# Microcontroller_sch_v22_4.net
KiCad netlist of a schematic drawn in Altium Designer
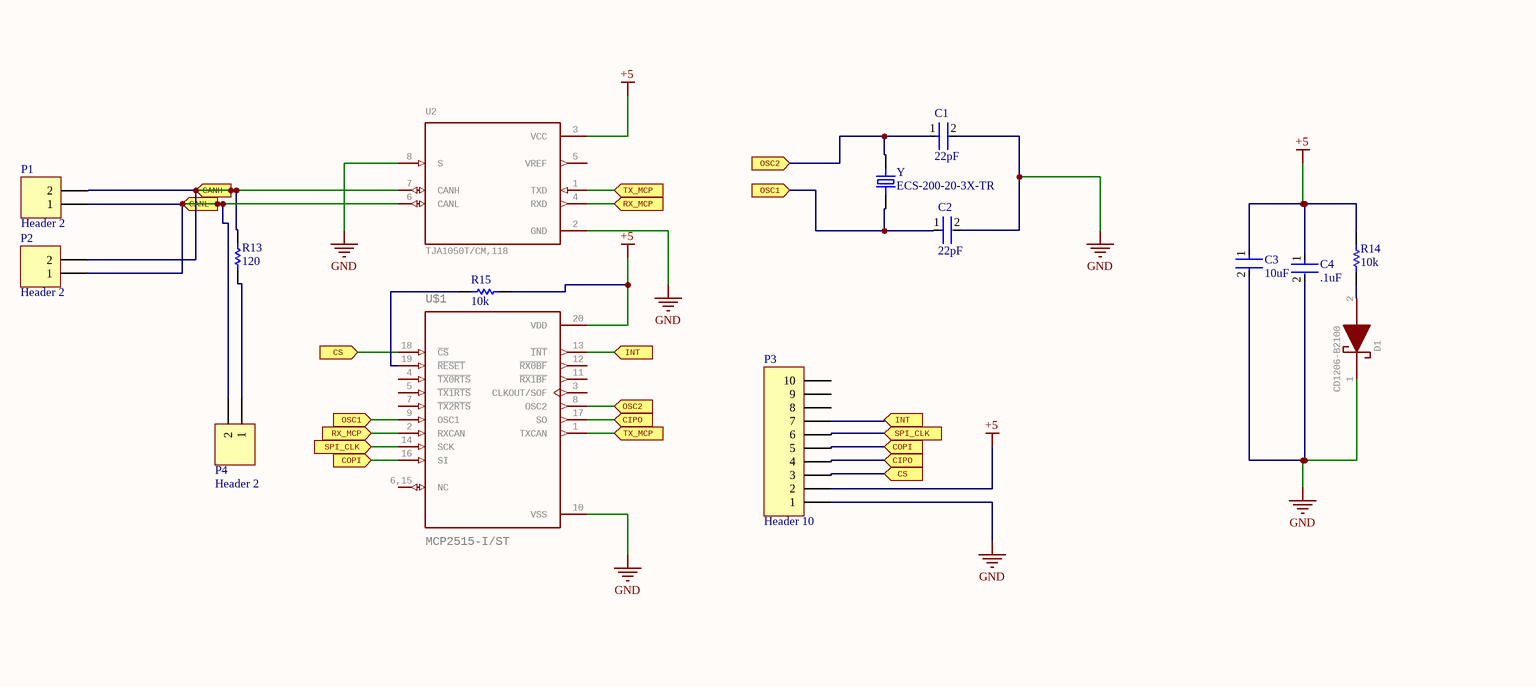
[diagram p0: Microcontroller_sch_v22_4.SchDoc]

(export (version "E")
  (design (tool "Eeschema 10.0.6"))
  (components
    (comp (ref "C1")
      (value "22pF")
      (footprint "FP-GRM21B-0_15-IPC_C")
      (description "Chip Multilayer Ceramic Capacitors for General Purpose, 0805, 10uF, X5R, 15%, 10%, 25V")
      (fields (field (name "VOLTAGE") "25V") (field (name "TOLERANCE") "10%"))
      (libsource (lib "Altium Content Vault") (part "b4654b650e69147ec39a6b967a45e02"))
    )
    (comp (ref "C2")
      (value "22pF")
      (footprint "FP-GRM21B-0_15-IPC_C")
      (description "Chip Multilayer Ceramic Capacitors for General Purpose, 0805, 10uF, X5R, 15%, 10%, 25V")
      (fields (field (name "VOLTAGE") "25V") (field (name "TOLERANCE") "10%"))
      (libsource (lib "Altium Content Vault") (part "b4654b650e69147ec39a6b967a45e02"))
    )
    (comp (ref "C3")
      (value "10uF")
      (footprint "FP-GRM21B-0_15-IPC_C")
      (description "Chip Multilayer Ceramic Capacitors for General Purpose, 0805, 10uF, X5R, 15%, 10%, 25V")
      (fields (field (name "VOLTAGE") "25V") (field (name "TOLERANCE") "10%"))
      (libsource (lib "Altium Content Vault") (part "b4654b650e69147ec39a6b967a45e02"))
    )
    (comp (ref "C4")
      (value ".1uF")
      (footprint "FP-GRM21B-0_15-IPC_C")
      (description "Chip Multilayer Ceramic Capacitors for General Purpose, 0805, 10uF, X5R, 15%, 10%, 25V")
      (fields (field (name "VOLTAGE") "25V") (field (name "TOLERANCE") "10%"))
      (libsource (lib "Altium Content Vault") (part "b4654b650e69147ec39a6b967a45e02"))
    )
    (comp (ref "D1")
      (value "CD1206-B2100")
      (footprint "DIOC3419X116N")
      (description "Schottky Diodes & Rectifiers CHIP DIODE   Source:  Datasheet")
      (fields (field (name "MOUSER_PART_NUMBER") "652-CD1206-B2100"))
      (libsource (lib "CD1206-B2100") (part "CD1206-B2100"))
    )
    (comp (ref "P1")
      (value "Header 2")
      (footprint "HDR1X2")
      (description "Header, 2-Pin")
      (fields (field (name "PUBLISHER") "Altium Limited"))
      (libsource (lib "") (part "Header 2_1"))
    )
    (comp (ref "P2")
      (value "Header 2")
      (footprint "HDR1X2")
      (description "Header, 2-Pin")
      (fields (field (name "PUBLISHER") "Altium Limited"))
      (libsource (lib "") (part "Header 2_1"))
    )
    (comp (ref "P3")
      (value "Header 10")
      (footprint "HDR1X10")
      (description "Header, 10-Pin")
      (fields (field (name "PUBLISHER") "Altium Limited"))
      (libsource (lib "Miscellaneous Connectors") (part "Header 10"))
    )
    (comp (ref "P4")
      (value "Header 2")
      (footprint "HDR1X2")
      (description "Header, 2-Pin")
      (fields (field (name "PUBLISHER") "Altium Limited"))
      (libsource (lib "Miscellaneous Connectors") (part "Header 2"))
    )
    (comp (ref "R13")
      (value "120")
      (footprint "RESC2013X50X30LL20T20")
      (fields (field (name "MANUFACTURER") "Vishay Dale") (field (name "PART NUMBER") "CRCW08050000Z0EA"))
      (libsource (lib "Altium Content Vault") (part "RES"))
    )
    (comp (ref "R14")
      (value "10k")
      (footprint "RESC2013X50X30LL20T20")
      (fields (field (name "MANUFACTURER") "Vishay Dale") (field (name "PART NUMBER") "CRCW08050000Z0EA"))
      (libsource (lib "Altium Content Vault") (part "RES"))
    )
    (comp (ref "R15")
      (value "10k")
      (footprint "RESC2013X50X30LL20T20")
      (fields (field (name "MANUFACTURER") "Vishay Dale") (field (name "PART NUMBER") "CRCW08050000Z0EA"))
      (libsource (lib "Altium Content Vault") (part "RES"))
    )
    (comp (ref "U$1")
      (value "MCP2515-I/ST")
      (footprint "SOP65P640X110-20N")
      (description "Check availability")
      (fields (field (name "MF") "Microchip"))
      (libsource (lib "MCP2515-I_ST") (part "MCP2515-I/ST"))
    )
    (comp (ref "U2")
      (value "TJA1050T/CM,118")
      (footprint "SOIC127P600X175-8N")
      (description "1/1 Transceiver Half CANbus 8-SO")
      (fields (field (name "MANUFACTURER") "NXP USA"))
      (libsource (lib "TJA1050T_CM_118") (part "TJA1050T/CM,118"))
    )
    (comp (ref "Y")
      (value "ECS-200-20-3X-TR")
      (footprint "XTAL_ECS-200-20-3X-TR")
      (description "20MHz Â± 30ppm Cristal 20pF 50 Ohms HC-49 / US")
      (fields (field (name "MF") "ECS Inc.") (field (name "DIGI-KEY_PART_NUMBER") "XC1779CT-ND"))
      (libsource (lib "ECS-200-20-3X-TR") (part "ECS-200-20-3X-TR"))
    )
  )
  (nets
    (net (code "1") (name "+5") (class "Default")
      (node (ref "C3") (pin "1") (pinfunction "1_1") (pintype "passive"))
      (node (ref "C4") (pin "1") (pinfunction "1_1") (pintype "passive"))
      (node (ref "P3") (pin "2") (pinfunction "2_2") (pintype "passive"))
      (node (ref "R14") (pin "1") (pinfunction "1_1") (pintype "passive"))
      (node (ref "R15") (pin "1") (pinfunction "1_1") (pintype "passive"))
      (node (ref "U$1") (pin "20") (pinfunction "VDD_20") (pintype "power_in"))
      (node (ref "U2") (pin "3") (pinfunction "VCC_3") (pintype "power_in"))
    )
    (net (code "2") (name "/CANH") (class "Default")
      (node (ref "P1") (pin "2") (pinfunction "2_2") (pintype "passive"))
      (node (ref "P2") (pin "2") (pinfunction "2_2") (pintype "passive"))
      (node (ref "R13") (pin "2") (pinfunction "2_2") (pintype "passive"))
      (node (ref "U2") (pin "7") (pinfunction "CANH_7") (pintype "bidirectional"))
    )
    (net (code "3") (name "/CANL") (class "Default")
      (node (ref "P1") (pin "1") (pinfunction "1_1") (pintype "passive"))
      (node (ref "P2") (pin "1") (pinfunction "1_1") (pintype "passive"))
      (node (ref "P4") (pin "2") (pinfunction "2_2") (pintype "passive"))
      (node (ref "U2") (pin "6") (pinfunction "CANL_6") (pintype "bidirectional"))
    )
    (net (code "4") (name "/CIPO") (class "Default")
      (node (ref "P3") (pin "4") (pinfunction "4_4") (pintype "passive"))
      (node (ref "U$1") (pin "17") (pinfunction "SO_17") (pintype "output"))
    )
    (net (code "5") (name "/COPI") (class "Default")
      (node (ref "P3") (pin "5") (pinfunction "5_5") (pintype "passive"))
      (node (ref "U$1") (pin "16") (pinfunction "SI_16") (pintype "input"))
    )
    (net (code "6") (name "/CS") (class "Default")
      (node (ref "P3") (pin "3") (pinfunction "3_3") (pintype "passive"))
      (node (ref "U$1") (pin "18") (pinfunction "~{CS}_18") (pintype "input"))
    )
    (net (code "7") (name "/INT") (class "Default")
      (node (ref "P3") (pin "7") (pinfunction "7_7") (pintype "passive"))
      (node (ref "U$1") (pin "13") (pinfunction "~{INT}_13") (pintype "output"))
    )
    (net (code "8") (name "/OSC1") (class "Default")
      (node (ref "C2") (pin "1") (pinfunction "1_1") (pintype "passive"))
      (node (ref "U$1") (pin "9") (pinfunction "OSC1_9") (pintype "input"))
      (node (ref "Y") (pin "1") (pinfunction "1_1") (pintype "passive"))
    )
    (net (code "9") (name "/OSC2") (class "Default")
      (node (ref "C1") (pin "1") (pinfunction "1_1") (pintype "passive"))
      (node (ref "U$1") (pin "8") (pinfunction "OSC2_8") (pintype "output"))
      (node (ref "Y") (pin "2") (pinfunction "2_2") (pintype "passive"))
    )
    (net (code "10") (name "/RX_MCP") (class "Default")
      (node (ref "U$1") (pin "2") (pinfunction "RXCAN_2") (pintype "input"))
      (node (ref "U2") (pin "4") (pinfunction "RXD_4") (pintype "output"))
    )
    (net (code "11") (name "/SPI_CLK") (class "Default")
      (node (ref "P3") (pin "6") (pinfunction "6_6") (pintype "passive"))
      (node (ref "U$1") (pin "14") (pinfunction "SCK_14") (pintype "input"))
    )
    (net (code "12") (name "/TX_MCP") (class "Default")
      (node (ref "U$1") (pin "1") (pinfunction "TXCAN_1") (pintype "output"))
      (node (ref "U2") (pin "1") (pinfunction "TXD_1") (pintype "input"))
    )
    (net (code "13") (name "GND") (class "Default")
      (node (ref "C1") (pin "2") (pinfunction "2_2") (pintype "passive"))
      (node (ref "C2") (pin "2") (pinfunction "2_2") (pintype "passive"))
      (node (ref "C3") (pin "2") (pinfunction "2_2") (pintype "passive"))
      (node (ref "C4") (pin "2") (pinfunction "2_2") (pintype "passive"))
      (node (ref "D1") (pin "1") (pinfunction "K_1") (pintype "bidirectional"))
      (node (ref "P3") (pin "1") (pinfunction "1_1") (pintype "passive"))
      (node (ref "U$1") (pin "10") (pinfunction "VSS_10") (pintype "power_in"))
      (node (ref "U2") (pin "2") (pinfunction "GND_2") (pintype "power_in"))
      (node (ref "U2") (pin "8") (pinfunction "S_8") (pintype "input"))
    )
    (net (code "14") (name "Net-(D1-A)") (class "Default")
      (node (ref "D1") (pin "2") (pinfunction "A_2") (pintype "bidirectional"))
      (node (ref "R14") (pin "2") (pinfunction "2_2") (pintype "passive"))
    )
    (net (code "15") (name "Net-(P4-Pad1)") (class "Default")
      (node (ref "P4") (pin "1") (pinfunction "1_1") (pintype "passive"))
      (node (ref "R13") (pin "1") (pinfunction "1_1") (pintype "passive"))
    )
    (net (code "16") (name "Net-(U$1-~{RESET})") (class "Default")
      (node (ref "R15") (pin "2") (pinfunction "2_2") (pintype "passive"))
      (node (ref "U$1") (pin "19") (pinfunction "~{RESET}_19") (pintype "input"))
    )
    (net (code "17") (name "unconnected-(P3-Pad8)") (class "Default")
      (node (ref "P3") (pin "8") (pinfunction "8_8") (pintype "passive"))
    )
    (net (code "18") (name "unconnected-(P3-Pad9)") (class "Default")
      (node (ref "P3") (pin "9") (pinfunction "9_9") (pintype "passive"))
    )
    (net (code "19") (name "unconnected-(P3-Pad10)") (class "Default")
      (node (ref "P3") (pin "10") (pinfunction "10_10") (pintype "passive"))
    )
    (net (code "20") (name "unconnected-(U$1-CLKOUT{slash}SOF-Pad3)") (class "Default")
      (node (ref "U$1") (pin "3") (pinfunction "CLKOUT/SOF_3") (pintype "output"))
    )
    (net (code "21") (name "unconnected-(U$1-NC-Pad6)") (class "Default")
      (node (ref "U$1") (pin "6") (pinfunction "NC_6") (pintype "bidirectional"))
      (node (ref "U$1") (pin "15") (pinfunction "NC_15") (pintype "bidirectional"))
    )
    (net (code "22") (name "unconnected-(U$1-~{RX0BF}-Pad12)") (class "Default")
      (node (ref "U$1") (pin "12") (pinfunction "~{RX0BF}_12") (pintype "output"))
    )
    (net (code "23") (name "unconnected-(U$1-~{RX1BF}-Pad11)") (class "Default")
      (node (ref "U$1") (pin "11") (pinfunction "~{RX1BF}_11") (pintype "output"))
    )
    (net (code "24") (name "unconnected-(U$1-~{TX0RTS}-Pad4)") (class "Default")
      (node (ref "U$1") (pin "4") (pinfunction "~{TX0RTS}_4") (pintype "input"))
    )
    (net (code "25") (name "unconnected-(U$1-~{TX1RTS}-Pad5)") (class "Default")
      (node (ref "U$1") (pin "5") (pinfunction "~{TX1RTS}_5") (pintype "input"))
    )
    (net (code "26") (name "unconnected-(U$1-~{TX2RTS}-Pad7)") (class "Default")
      (node (ref "U$1") (pin "7") (pinfunction "~{TX2RTS}_7") (pintype "input"))
    )
    (net (code "27") (name "unconnected-(U2-VREF-Pad5)") (class "Default")
      (node (ref "U2") (pin "5") (pinfunction "VREF_5") (pintype "output"))
    )
  )
)
